# power-dac.net
KiCad netlist of a schematic drawn in Altium Designer
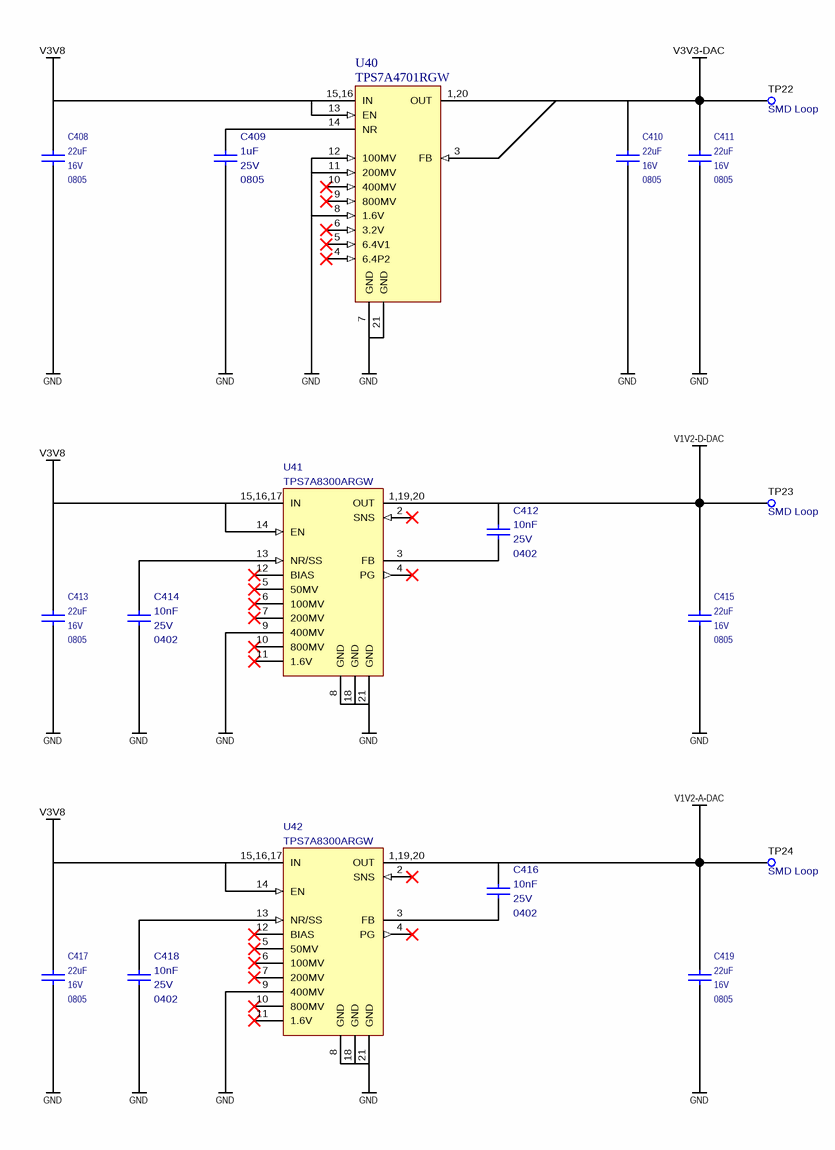
[diagram p0: power-dac.SchDoc]

(export (version "E")
  (design (tool "Eeschema 10.0.6"))
  (components
    (comp (ref "C408")
      (value "22uF")
      (footprint "generic:CAPC200X125X145L45N")
      (description "Ceramic Capacitor 22uF ±20% 16V X5R 0805")
      (fields
        (field (name "MANUFACTURER") "Samsung Electro-Mechanics")
        (field (name "VOLTAGE") "16V")
        (field (name "PACKAGE") "0805")
        (field (name "TOLERANCE") "±20%")
      )
      (libsource (lib "generic") (part "CAP 0603"))
    )
    (comp (ref "C409")
      (value "1uF")
      (footprint "CAPC160X80X90L20N")
      (description "Ceramic Capacitor 1uF ±10% 25V X7R 0805")
      (fields
        (field (name "MANUFACTURER") "Taiyo Yuden")
        (field (name "TOLERANCE") "±10%")
        (field (name "PACKAGE") "0805")
        (field (name "VOLTAGE") "25V")
      )
      (libsource (lib "capacitors") (part "CAP"))
    )
    (comp (ref "C410")
      (value "22uF")
      (footprint "generic:CAPC200X125X145L45N")
      (description "Ceramic Capacitor 22uF ±20% 16V X5R 0805")
      (fields
        (field (name "MANUFACTURER") "Samsung Electro-Mechanics")
        (field (name "VOLTAGE") "16V")
        (field (name "PACKAGE") "0805")
        (field (name "TOLERANCE") "±20%")
      )
      (libsource (lib "generic") (part "CAP 0603"))
    )
    (comp (ref "C411")
      (value "22uF")
      (footprint "generic:CAPC200X125X145L45N")
      (description "Ceramic Capacitor 22uF ±20% 16V X5R 0805")
      (fields
        (field (name "MANUFACTURER") "Samsung Electro-Mechanics")
        (field (name "VOLTAGE") "16V")
        (field (name "PACKAGE") "0805")
        (field (name "TOLERANCE") "±20%")
      )
      (libsource (lib "generic") (part "CAP 0603"))
    )
    (comp (ref "C412")
      (value "10nF")
      (footprint "generic:CAPC100X50X55L25N")
      (description "Ceramic Capacitor 10nF ±10% 25V X7R 0402")
      (fields
        (field (name "MANUFACTURER") "Taiyo Yuden")
        (field (name "TOLERANCE") "±10%")
        (field (name "PACKAGE") "0402")
        (field (name "VOLTAGE") "25V")
      )
      (libsource (lib "capacitors") (part "CAP"))
    )
    (comp (ref "C413")
      (value "22uF")
      (footprint "generic:CAPC200X125X145L45N")
      (description "Ceramic Capacitor 22uF ±20% 16V X5R 0805")
      (fields
        (field (name "MANUFACTURER") "Samsung Electro-Mechanics")
        (field (name "VOLTAGE") "16V")
        (field (name "PACKAGE") "0805")
        (field (name "TOLERANCE") "±20%")
      )
      (libsource (lib "generic") (part "CAP 0603"))
    )
    (comp (ref "C414")
      (value "10nF")
      (footprint "generic:CAPC100X50X55L25N")
      (description "Ceramic Capacitor 10nF ±10% 25V X7R 0402")
      (fields
        (field (name "MANUFACTURER") "Taiyo Yuden")
        (field (name "TOLERANCE") "±10%")
        (field (name "PACKAGE") "0402")
        (field (name "VOLTAGE") "25V")
      )
      (libsource (lib "capacitors") (part "CAP"))
    )
    (comp (ref "C415")
      (value "22uF")
      (footprint "generic:CAPC200X125X145L45N")
      (description "Ceramic Capacitor 22uF ±20% 16V X5R 0805")
      (fields
        (field (name "MANUFACTURER") "Samsung Electro-Mechanics")
        (field (name "VOLTAGE") "16V")
        (field (name "PACKAGE") "0805")
        (field (name "TOLERANCE") "±20%")
      )
      (libsource (lib "generic") (part "CAP 0603"))
    )
    (comp (ref "C416")
      (value "10nF")
      (footprint "generic:CAPC100X50X55L25N")
      (description "Ceramic Capacitor 10nF ±10% 25V X7R 0402")
      (fields
        (field (name "MANUFACTURER") "Taiyo Yuden")
        (field (name "TOLERANCE") "±10%")
        (field (name "PACKAGE") "0402")
        (field (name "VOLTAGE") "25V")
      )
      (libsource (lib "capacitors") (part "CAP"))
    )
    (comp (ref "C417")
      (value "22uF")
      (footprint "generic:CAPC200X125X145L45N")
      (description "Ceramic Capacitor 22uF ±20% 16V X5R 0805")
      (fields
        (field (name "MANUFACTURER") "Samsung Electro-Mechanics")
        (field (name "VOLTAGE") "16V")
        (field (name "PACKAGE") "0805")
        (field (name "TOLERANCE") "±20%")
      )
      (libsource (lib "generic") (part "CAP 0603"))
    )
    (comp (ref "C418")
      (value "10nF")
      (footprint "generic:CAPC100X50X55L25N")
      (description "Ceramic Capacitor 10nF ±10% 25V X7R 0402")
      (fields
        (field (name "MANUFACTURER") "Taiyo Yuden")
        (field (name "TOLERANCE") "±10%")
        (field (name "PACKAGE") "0402")
        (field (name "VOLTAGE") "25V")
      )
      (libsource (lib "capacitors") (part "CAP"))
    )
    (comp (ref "C419")
      (value "22uF")
      (footprint "generic:CAPC200X125X145L45N")
      (description "Ceramic Capacitor 22uF ±20% 16V X5R 0805")
      (fields
        (field (name "MANUFACTURER") "Samsung Electro-Mechanics")
        (field (name "VOLTAGE") "16V")
        (field (name "PACKAGE") "0805")
        (field (name "TOLERANCE") "±20%")
      )
      (libsource (lib "generic") (part "CAP 0603"))
    )
    (comp (ref "TP22")
      (value "5015")
      (footprint "keystone:5015")
      (description "Test Point SMD")
      (fields (field (name "MANUFACTURER") "Keystone") (field (name "NOTES") "SMD Loop"))
      (libsource (lib "generic") (part "TEST_POINT_SMD_50"))
    )
    (comp (ref "TP23")
      (value "5015")
      (footprint "keystone:5015")
      (description "Test Point SMD")
      (fields (field (name "MANUFACTURER") "Keystone") (field (name "NOTES") "SMD Loop"))
      (libsource (lib "generic") (part "TEST_POINT_SMD_50"))
    )
    (comp (ref "TP24")
      (value "5015")
      (footprint "keystone:5015")
      (description "Test Point SMD")
      (fields (field (name "MANUFACTURER") "Keystone") (field (name "NOTES") "SMD Loop"))
      (libsource (lib "generic") (part "TEST_POINT_SMD_50"))
    )
    (comp (ref "U40")
      (value "TPS7A4701RGW")
      (footprint "QFN65P500X500X100-21N")
      (description "Low-Dropout Linear Regulator 20-VQFN")
      (fields (field (name "MANUFACTURER") "Texas Instruments"))
      (libsource (lib "ti") (part "TPS7A4701RGW_1"))
    )
    (comp (ref "U41")
      (value "TPS7A8300ARGW")
      (footprint "texas_instruments:QFN65P500X500X100-21N")
      (description "LDO Regulator, 2A, VQFN-20")
      (fields (field (name "MANUFACTURER") "Texas Instruments"))
      (libsource (lib "ti") (part "TPS7A8300ARGW"))
    )
    (comp (ref "U42")
      (value "TPS7A8300ARGW")
      (footprint "texas_instruments:QFN65P500X500X100-21N")
      (description "LDO Regulator, 2A, VQFN-20")
      (fields (field (name "MANUFACTURER") "Texas Instruments"))
      (libsource (lib "ti") (part "TPS7A8300ARGW"))
    )
  )
  (nets
    (net (code "1") (name "GND") (class "Default")
      (node (ref "C408") (pin "1") (pinfunction "1_1") (pintype "passive"))
      (node (ref "C409") (pin "2") (pinfunction "2_2") (pintype "passive"))
      (node (ref "C410") (pin "1") (pinfunction "1_1") (pintype "passive"))
      (node (ref "C411") (pin "1") (pinfunction "1_1") (pintype "passive"))
      (node (ref "C413") (pin "1") (pinfunction "1_1") (pintype "passive"))
      (node (ref "C414") (pin "2") (pinfunction "2_2") (pintype "passive"))
      (node (ref "C415") (pin "1") (pinfunction "1_1") (pintype "passive"))
      (node (ref "C417") (pin "1") (pinfunction "1_1") (pintype "passive"))
      (node (ref "C418") (pin "2") (pinfunction "2_2") (pintype "passive"))
      (node (ref "C419") (pin "1") (pinfunction "1_1") (pintype "passive"))
      (node (ref "U40") (pin "11") (pinfunction "200MV_11") (pintype "input"))
      (node (ref "U40") (pin "12") (pinfunction "100MV_12") (pintype "input"))
      (node (ref "U40") (pin "21") (pinfunction "GND_21") (pintype "power_in"))
      (node (ref "U40") (pin "7") (pinfunction "GND_7") (pintype "power_in"))
      (node (ref "U40") (pin "8") (pinfunction "1.6V_8") (pintype "input"))
      (node (ref "U41") (pin "18") (pinfunction "GND_18") (pintype "passive"))
      (node (ref "U41") (pin "21") (pinfunction "GND_21") (pintype "passive"))
      (node (ref "U41") (pin "8") (pinfunction "GND_8") (pintype "passive"))
      (node (ref "U41") (pin "9") (pinfunction "400MV_9") (pintype "passive"))
      (node (ref "U42") (pin "18") (pinfunction "GND_18") (pintype "passive"))
      (node (ref "U42") (pin "21") (pinfunction "GND_21") (pintype "passive"))
      (node (ref "U42") (pin "8") (pinfunction "GND_8") (pintype "passive"))
      (node (ref "U42") (pin "9") (pinfunction "400MV_9") (pintype "passive"))
    )
    (net (code "2") (name "Net-(U40-NR)") (class "Default")
      (node (ref "C409") (pin "1") (pinfunction "1_1") (pintype "passive"))
      (node (ref "U40") (pin "14") (pinfunction "NR_14") (pintype "passive"))
    )
    (net (code "3") (name "Net-(U41-FB)") (class "Default")
      (node (ref "C412") (pin "2") (pinfunction "2_2") (pintype "passive"))
      (node (ref "U41") (pin "3") (pinfunction "FB_3") (pintype "passive"))
    )
    (net (code "4") (name "Net-(U41-NR{slash}SS)") (class "Default")
      (node (ref "C414") (pin "1") (pinfunction "1_1") (pintype "passive"))
      (node (ref "U41") (pin "13") (pinfunction "NR/SS_13") (pintype "input"))
    )
    (net (code "5") (name "Net-(U42-FB)") (class "Default")
      (node (ref "C416") (pin "2") (pinfunction "2_2") (pintype "passive"))
      (node (ref "U42") (pin "3") (pinfunction "FB_3") (pintype "passive"))
    )
    (net (code "6") (name "Net-(U42-NR{slash}SS)") (class "Default")
      (node (ref "C418") (pin "1") (pinfunction "1_1") (pintype "passive"))
      (node (ref "U42") (pin "13") (pinfunction "NR/SS_13") (pintype "input"))
    )
    (net (code "7") (name "V1V2-A-DAC") (class "Default")
      (node (ref "C416") (pin "1") (pinfunction "1_1") (pintype "passive"))
      (node (ref "C419") (pin "2") (pinfunction "2_2") (pintype "passive"))
      (node (ref "TP24") (pin "1") (pinfunction "1_1") (pintype "passive"))
      (node (ref "U42") (pin "1") (pinfunction "OUT_1") (pintype "passive"))
      (node (ref "U42") (pin "19") (pinfunction "OUT_19") (pintype "passive"))
      (node (ref "U42") (pin "20") (pinfunction "OUT_20") (pintype "passive"))
    )
    (net (code "8") (name "V1V2-D-DAC") (class "Default")
      (node (ref "C412") (pin "1") (pinfunction "1_1") (pintype "passive"))
      (node (ref "C415") (pin "2") (pinfunction "2_2") (pintype "passive"))
      (node (ref "TP23") (pin "1") (pinfunction "1_1") (pintype "passive"))
      (node (ref "U41") (pin "1") (pinfunction "OUT_1") (pintype "passive"))
      (node (ref "U41") (pin "19") (pinfunction "OUT_19") (pintype "passive"))
      (node (ref "U41") (pin "20") (pinfunction "OUT_20") (pintype "passive"))
    )
    (net (code "9") (name "V3V3-DAC") (class "Default")
      (node (ref "C410") (pin "2") (pinfunction "2_2") (pintype "passive"))
      (node (ref "C411") (pin "2") (pinfunction "2_2") (pintype "passive"))
      (node (ref "TP22") (pin "1") (pinfunction "1_1") (pintype "passive"))
      (node (ref "U40") (pin "1") (pinfunction "OUT_1") (pintype "passive"))
      (node (ref "U40") (pin "20") (pinfunction "OUT_20") (pintype "passive"))
      (node (ref "U40") (pin "3") (pinfunction "FB_3") (pintype "input"))
    )
    (net (code "10") (name "V3V8") (class "Default")
      (node (ref "C408") (pin "2") (pinfunction "2_2") (pintype "passive"))
      (node (ref "C413") (pin "2") (pinfunction "2_2") (pintype "passive"))
      (node (ref "C417") (pin "2") (pinfunction "2_2") (pintype "passive"))
      (node (ref "U40") (pin "13") (pinfunction "EN_13") (pintype "input"))
      (node (ref "U40") (pin "15") (pinfunction "IN_15") (pintype "passive"))
      (node (ref "U40") (pin "16") (pinfunction "IN_16") (pintype "passive"))
      (node (ref "U41") (pin "14") (pinfunction "EN_14") (pintype "input"))
      (node (ref "U41") (pin "15") (pinfunction "IN_15") (pintype "passive"))
      (node (ref "U41") (pin "16") (pinfunction "IN_16") (pintype "passive"))
      (node (ref "U41") (pin "17") (pinfunction "IN_17") (pintype "passive"))
      (node (ref "U42") (pin "14") (pinfunction "EN_14") (pintype "input"))
      (node (ref "U42") (pin "15") (pinfunction "IN_15") (pintype "passive"))
      (node (ref "U42") (pin "16") (pinfunction "IN_16") (pintype "passive"))
      (node (ref "U42") (pin "17") (pinfunction "IN_17") (pintype "passive"))
    )
    (net (code "11") (name "unconnected-(U40-3.2V-Pad6)") (class "Default")
      (node (ref "U40") (pin "6") (pinfunction "3.2V_6") (pintype "input+no_connect"))
    )
    (net (code "12") (name "unconnected-(U40-6.4P2-Pad4)") (class "Default")
      (node (ref "U40") (pin "4") (pinfunction "6.4P2_4") (pintype "input+no_connect"))
    )
    (net (code "13") (name "unconnected-(U40-6.4V1-Pad5)") (class "Default")
      (node (ref "U40") (pin "5") (pinfunction "6.4V1_5") (pintype "input+no_connect"))
    )
    (net (code "14") (name "unconnected-(U40-400MV-Pad10)") (class "Default")
      (node (ref "U40") (pin "10") (pinfunction "400MV_10") (pintype "input+no_connect"))
    )
    (net (code "15") (name "unconnected-(U40-800MV-Pad9)") (class "Default")
      (node (ref "U40") (pin "9") (pinfunction "800MV_9") (pintype "input+no_connect"))
    )
    (net (code "16") (name "unconnected-(U41-1.6V-Pad11)") (class "Default")
      (node (ref "U41") (pin "11") (pinfunction "1.6V_11") (pintype "passive+no_connect"))
    )
    (net (code "17") (name "unconnected-(U41-50MV-Pad5)") (class "Default")
      (node (ref "U41") (pin "5") (pinfunction "50MV_5") (pintype "passive+no_connect"))
    )
    (net (code "18") (name "unconnected-(U41-100MV-Pad6)") (class "Default")
      (node (ref "U41") (pin "6") (pinfunction "100MV_6") (pintype "passive+no_connect"))
    )
    (net (code "19") (name "unconnected-(U41-200MV-Pad7)") (class "Default")
      (node (ref "U41") (pin "7") (pinfunction "200MV_7") (pintype "passive+no_connect"))
    )
    (net (code "20") (name "unconnected-(U41-800MV-Pad10)") (class "Default")
      (node (ref "U41") (pin "10") (pinfunction "800MV_10") (pintype "passive+no_connect"))
    )
    (net (code "21") (name "unconnected-(U41-BIAS-Pad12)") (class "Default")
      (node (ref "U41") (pin "12") (pinfunction "BIAS_12") (pintype "power_in+no_connect"))
    )
    (net (code "22") (name "unconnected-(U41-PG-Pad4)") (class "Default")
      (node (ref "U41") (pin "4") (pinfunction "PG_4") (pintype "output+no_connect"))
    )
    (net (code "23") (name "unconnected-(U41-SNS-Pad2)") (class "Default")
      (node (ref "U41") (pin "2") (pinfunction "SNS_2") (pintype "input+no_connect"))
    )
    (net (code "24") (name "unconnected-(U42-1.6V-Pad11)") (class "Default")
      (node (ref "U42") (pin "11") (pinfunction "1.6V_11") (pintype "passive+no_connect"))
    )
    (net (code "25") (name "unconnected-(U42-50MV-Pad5)") (class "Default")
      (node (ref "U42") (pin "5") (pinfunction "50MV_5") (pintype "passive+no_connect"))
    )
    (net (code "26") (name "unconnected-(U42-100MV-Pad6)") (class "Default")
      (node (ref "U42") (pin "6") (pinfunction "100MV_6") (pintype "passive+no_connect"))
    )
    (net (code "27") (name "unconnected-(U42-200MV-Pad7)") (class "Default")
      (node (ref "U42") (pin "7") (pinfunction "200MV_7") (pintype "passive+no_connect"))
    )
    (net (code "28") (name "unconnected-(U42-800MV-Pad10)") (class "Default")
      (node (ref "U42") (pin "10") (pinfunction "800MV_10") (pintype "passive+no_connect"))
    )
    (net (code "29") (name "unconnected-(U42-BIAS-Pad12)") (class "Default")
      (node (ref "U42") (pin "12") (pinfunction "BIAS_12") (pintype "power_in+no_connect"))
    )
    (net (code "30") (name "unconnected-(U42-PG-Pad4)") (class "Default")
      (node (ref "U42") (pin "4") (pinfunction "PG_4") (pintype "output+no_connect"))
    )
    (net (code "31") (name "unconnected-(U42-SNS-Pad2)") (class "Default")
      (node (ref "U42") (pin "2") (pinfunction "SNS_2") (pintype "input+no_connect"))
    )
  )
)
